# B137C.net
KiCad netlist of a schematic drawn in EAGLE
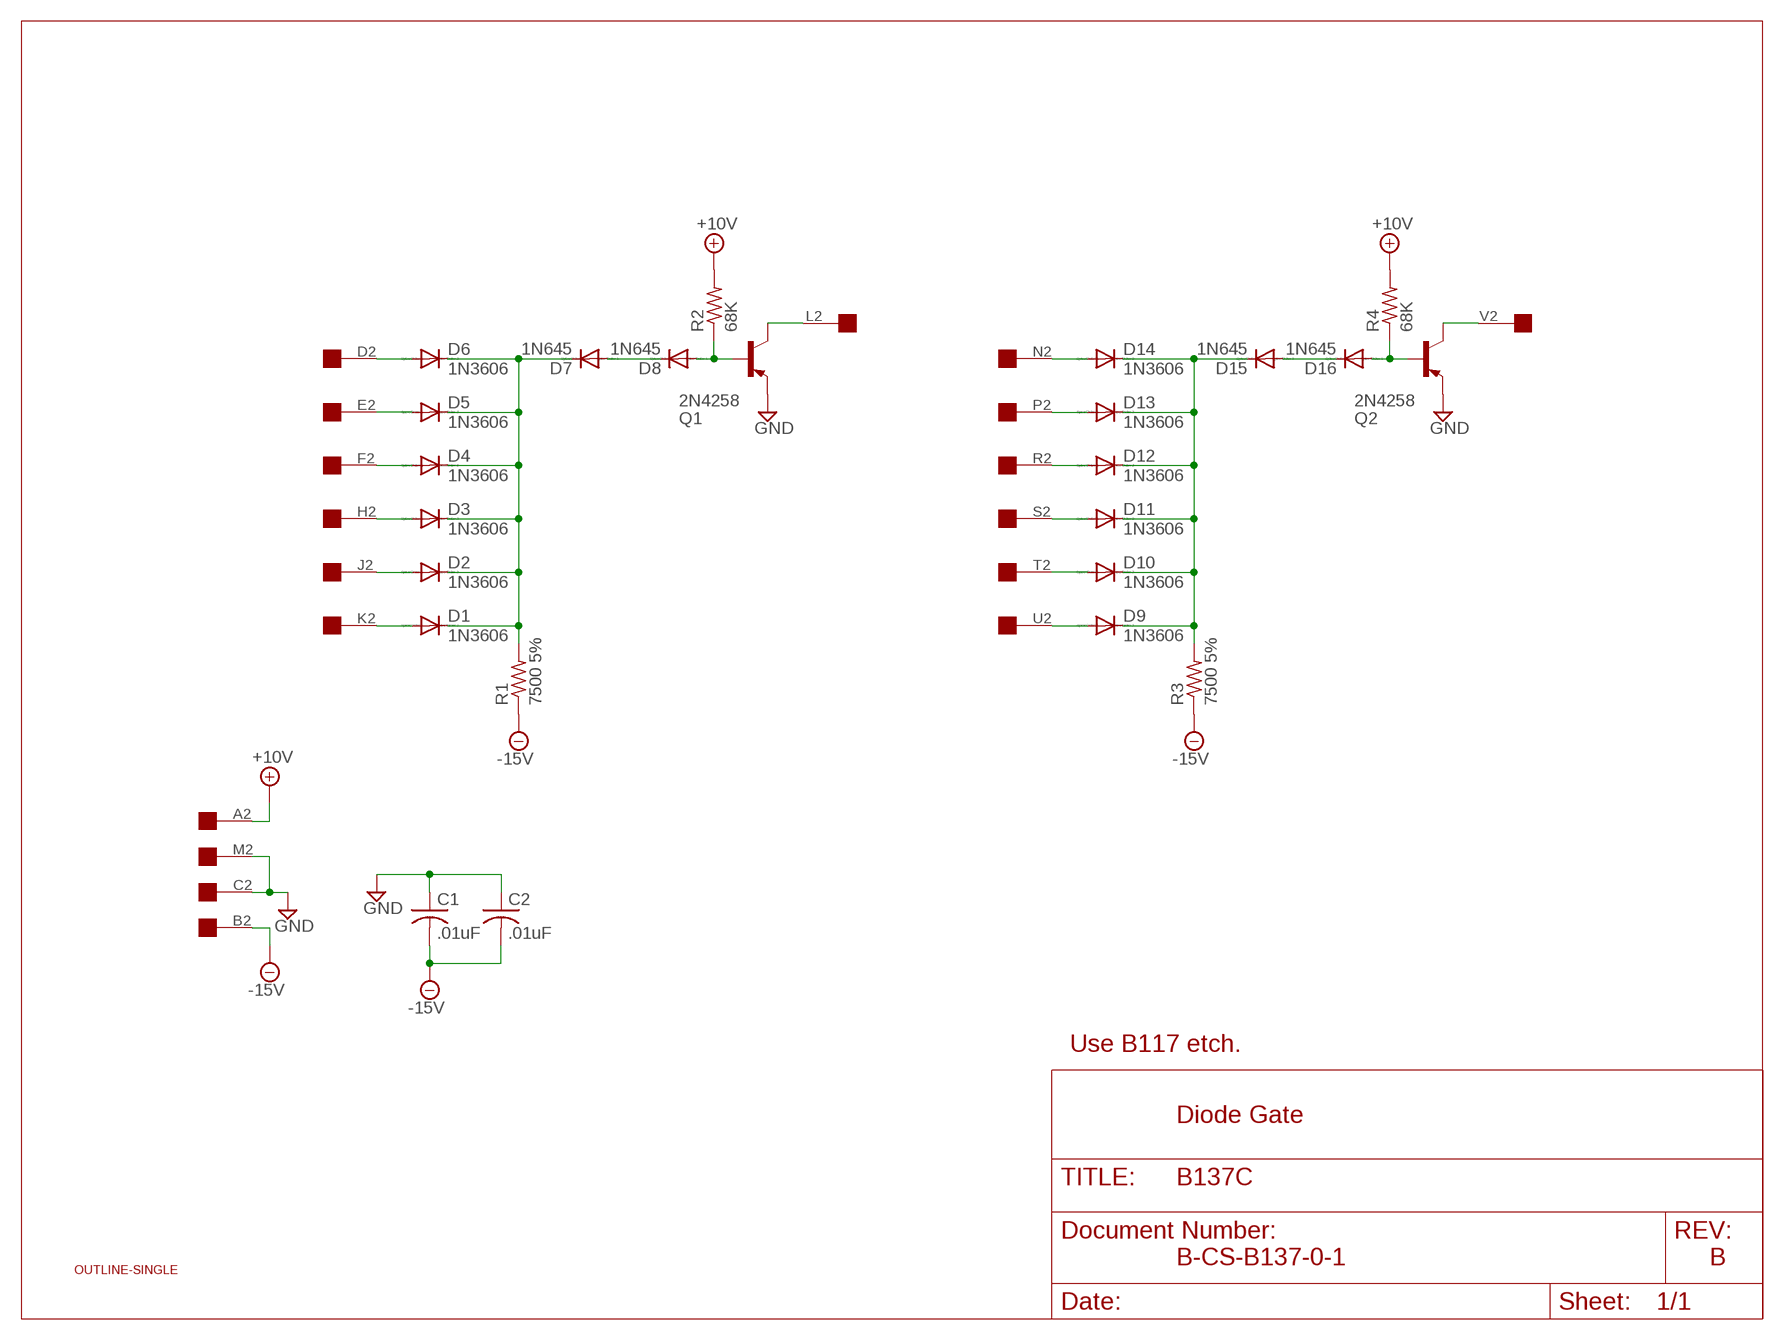
[diagram p0: schematic, sheet 1]

(export (version "E")
  (design (tool "Eeschema 10.0.6"))
  (components
    (comp (ref "C1")
      (value ".01uF")
      (footprint "eagle-import:C050-025X075")
      (libsource (lib "eagle-import") (part "C-US050-025X075"))
    )
    (comp (ref "C2")
      (value ".01uF")
      (footprint "eagle-import:C050-025X075")
      (libsource (lib "eagle-import") (part "C-US050-025X075"))
    )
    (comp (ref "D1")
      (value "1N3606")
      (footprint "eagle-import:DO35-10")
      (libsource (lib "eagle-import") (part "DIODE-DO35-10"))
    )
    (comp (ref "D2")
      (value "1N3606")
      (footprint "eagle-import:DO35-10")
      (libsource (lib "eagle-import") (part "DIODE-DO35-10"))
    )
    (comp (ref "D3")
      (value "1N3606")
      (footprint "eagle-import:DO35-10")
      (libsource (lib "eagle-import") (part "DIODE-DO35-10"))
    )
    (comp (ref "D4")
      (value "1N3606")
      (footprint "eagle-import:DO35-10")
      (libsource (lib "eagle-import") (part "DIODE-DO35-10"))
    )
    (comp (ref "D5")
      (value "1N3606")
      (footprint "eagle-import:DO35-10")
      (libsource (lib "eagle-import") (part "DIODE-DO35-10"))
    )
    (comp (ref "D6")
      (value "1N3606")
      (footprint "eagle-import:DO35-10")
      (libsource (lib "eagle-import") (part "DIODE-DO35-10"))
    )
    (comp (ref "D7")
      (value "1N645")
      (footprint "eagle-import:DO35-10")
      (libsource (lib "eagle-import") (part "DIODE-DO35-10"))
    )
    (comp (ref "D8")
      (value "1N645")
      (footprint "eagle-import:DO35-10")
      (libsource (lib "eagle-import") (part "DIODE-DO35-10"))
    )
    (comp (ref "D9")
      (value "1N3606")
      (footprint "eagle-import:DO35-10")
      (libsource (lib "eagle-import") (part "DIODE-DO35-10"))
    )
    (comp (ref "D10")
      (value "1N3606")
      (footprint "eagle-import:DO35-10")
      (libsource (lib "eagle-import") (part "DIODE-DO35-10"))
    )
    (comp (ref "D11")
      (value "1N3606")
      (footprint "eagle-import:DO35-10")
      (libsource (lib "eagle-import") (part "DIODE-DO35-10"))
    )
    (comp (ref "D12")
      (value "1N3606")
      (footprint "eagle-import:DO35-10")
      (libsource (lib "eagle-import") (part "DIODE-DO35-10"))
    )
    (comp (ref "D13")
      (value "1N3606")
      (footprint "eagle-import:DO35-10")
      (libsource (lib "eagle-import") (part "DIODE-DO35-10"))
    )
    (comp (ref "D14")
      (value "1N3606")
      (footprint "eagle-import:DO35-10")
      (libsource (lib "eagle-import") (part "DIODE-DO35-10"))
    )
    (comp (ref "D15")
      (value "1N645")
      (footprint "eagle-import:DO35-10")
      (libsource (lib "eagle-import") (part "DIODE-DO35-10"))
    )
    (comp (ref "D16")
      (value "1N645")
      (footprint "eagle-import:DO35-10")
      (libsource (lib "eagle-import") (part "DIODE-DO35-10"))
    )
    (comp (ref "Q1")
      (value "2N4258")
      (footprint "eagle-import:TO5")
      (libsource (lib "eagle-import") (part "-PNP-TO5"))
    )
    (comp (ref "Q2")
      (value "2N4258")
      (footprint "eagle-import:TO5")
      (libsource (lib "eagle-import") (part "-PNP-TO5"))
    )
    (comp (ref "R1")
      (value "7500 5%")
      (footprint "eagle-import:0207_10")
      (libsource (lib "eagle-import") (part "R-US_0207/10"))
    )
    (comp (ref "R2")
      (value "68K")
      (footprint "eagle-import:0207_10")
      (libsource (lib "eagle-import") (part "R-US_0207/10"))
    )
    (comp (ref "R3")
      (value "7500 5%")
      (footprint "eagle-import:0207_10")
      (libsource (lib "eagle-import") (part "R-US_0207/10"))
    )
    (comp (ref "R4")
      (value "68K")
      (footprint "eagle-import:0207_10")
      (libsource (lib "eagle-import") (part "R-US_0207/10"))
    )
    (comp (ref "U$1")
      (value "OUTLINE-SINGLE")
      (footprint "eagle-import:SINGLE")
      (libsource (lib "eagle-import") (part "OUTLINE-SINGLE"))
    )
    (comp (ref "U$2")
      (value "EDGE-1")
      (footprint "eagle-import:EDGE-CON1")
      (libsource (lib "eagle-import") (part "EDGE-1"))
    )
  )
  (nets
    (net (code "1") (name "+10V") (class "Default")
      (node (ref "R2") (pin "2") (pinfunction "2_2") (pintype "passive"))
      (node (ref "R4") (pin "2") (pinfunction "2_2") (pintype "passive"))
      (node (ref "U$2") (pin "A2") (pinfunction "1_A2") (pintype "bidirectional"))
    )
    (net (code "2") (name "-15V") (class "Default")
      (node (ref "C1") (pin "2") (pinfunction "2_2") (pintype "passive"))
      (node (ref "C2") (pin "2") (pinfunction "2_2") (pintype "passive"))
      (node (ref "R1") (pin "1") (pinfunction "1_1") (pintype "passive"))
      (node (ref "R3") (pin "1") (pinfunction "1_1") (pintype "passive"))
      (node (ref "U$2") (pin "B2") (pinfunction "1_B2") (pintype "bidirectional"))
    )
    (net (code "3") (name "GND") (class "Default")
      (node (ref "C1") (pin "1") (pinfunction "1_1") (pintype "passive"))
      (node (ref "C2") (pin "1") (pinfunction "1_1") (pintype "passive"))
      (node (ref "Q1") (pin "1") (pinfunction "E_1") (pintype "passive"))
      (node (ref "Q2") (pin "1") (pinfunction "E_1") (pintype "passive"))
      (node (ref "U$2") (pin "C2") (pinfunction "1_C2") (pintype "bidirectional"))
      (node (ref "U$2") (pin "M2") (pinfunction "1_M2") (pintype "bidirectional"))
    )
    (net (code "4") (name "Net-(D1-PadC)") (class "Default")
      (node (ref "D1") (pin "C") (pinfunction "C_C") (pintype "passive"))
      (node (ref "D2") (pin "C") (pinfunction "C_C") (pintype "passive"))
      (node (ref "D3") (pin "C") (pinfunction "C_C") (pintype "passive"))
      (node (ref "D4") (pin "C") (pinfunction "C_C") (pintype "passive"))
      (node (ref "D5") (pin "C") (pinfunction "C_C") (pintype "passive"))
      (node (ref "D6") (pin "C") (pinfunction "C_C") (pintype "passive"))
      (node (ref "D7") (pin "C") (pinfunction "C_C") (pintype "passive"))
      (node (ref "R1") (pin "2") (pinfunction "2_2") (pintype "passive"))
    )
    (net (code "5") (name "Net-(D7-PadA)") (class "Default")
      (node (ref "D7") (pin "A") (pinfunction "A_A") (pintype "passive"))
      (node (ref "D8") (pin "C") (pinfunction "C_C") (pintype "passive"))
    )
    (net (code "6") (name "Net-(D10-PadC)") (class "Default")
      (node (ref "D10") (pin "C") (pinfunction "C_C") (pintype "passive"))
      (node (ref "D11") (pin "C") (pinfunction "C_C") (pintype "passive"))
      (node (ref "D12") (pin "C") (pinfunction "C_C") (pintype "passive"))
      (node (ref "D13") (pin "C") (pinfunction "C_C") (pintype "passive"))
      (node (ref "D14") (pin "C") (pinfunction "C_C") (pintype "passive"))
      (node (ref "D15") (pin "C") (pinfunction "C_C") (pintype "passive"))
      (node (ref "D9") (pin "C") (pinfunction "C_C") (pintype "passive"))
      (node (ref "R3") (pin "2") (pinfunction "2_2") (pintype "passive"))
    )
    (net (code "7") (name "Net-(D15-PadA)") (class "Default")
      (node (ref "D15") (pin "A") (pinfunction "A_A") (pintype "passive"))
      (node (ref "D16") (pin "C") (pinfunction "C_C") (pintype "passive"))
    )
    (net (code "8") (name "Net-(Q1-B)") (class "Default")
      (node (ref "D8") (pin "A") (pinfunction "A_A") (pintype "passive"))
      (node (ref "Q1") (pin "2") (pinfunction "B_2") (pintype "passive"))
      (node (ref "R2") (pin "1") (pinfunction "1_1") (pintype "passive"))
    )
    (net (code "9") (name "Net-(Q1-C)") (class "Default")
      (node (ref "Q1") (pin "3") (pinfunction "C_3") (pintype "passive"))
      (node (ref "U$2") (pin "L2") (pinfunction "1_L2") (pintype "bidirectional"))
    )
    (net (code "10") (name "Net-(Q2-B)") (class "Default")
      (node (ref "D16") (pin "A") (pinfunction "A_A") (pintype "passive"))
      (node (ref "Q2") (pin "2") (pinfunction "B_2") (pintype "passive"))
      (node (ref "R4") (pin "1") (pinfunction "1_1") (pintype "passive"))
    )
    (net (code "11") (name "Net-(Q2-C)") (class "Default")
      (node (ref "Q2") (pin "3") (pinfunction "C_3") (pintype "passive"))
      (node (ref "U$2") (pin "V2") (pinfunction "1_V2") (pintype "bidirectional"))
    )
    (net (code "12") (name "Net-(U$2D-1)") (class "Default")
      (node (ref "D6") (pin "A") (pinfunction "A_A") (pintype "passive"))
      (node (ref "U$2") (pin "D2") (pinfunction "1_D2") (pintype "bidirectional"))
    )
    (net (code "13") (name "Net-(U$2E-1)") (class "Default")
      (node (ref "D5") (pin "A") (pinfunction "A_A") (pintype "passive"))
      (node (ref "U$2") (pin "E2") (pinfunction "1_E2") (pintype "bidirectional"))
    )
    (net (code "14") (name "Net-(U$2F-1)") (class "Default")
      (node (ref "D4") (pin "A") (pinfunction "A_A") (pintype "passive"))
      (node (ref "U$2") (pin "F2") (pinfunction "1_F2") (pintype "bidirectional"))
    )
    (net (code "15") (name "Net-(U$2G-1)") (class "Default")
      (node (ref "D3") (pin "A") (pinfunction "A_A") (pintype "passive"))
      (node (ref "U$2") (pin "H2") (pinfunction "1_H2") (pintype "bidirectional"))
    )
    (net (code "16") (name "Net-(U$2H-1)") (class "Default")
      (node (ref "D2") (pin "A") (pinfunction "A_A") (pintype "passive"))
      (node (ref "U$2") (pin "J2") (pinfunction "1_J2") (pintype "bidirectional"))
    )
    (net (code "17") (name "Net-(U$2I-1)") (class "Default")
      (node (ref "D1") (pin "A") (pinfunction "A_A") (pintype "passive"))
      (node (ref "U$2") (pin "K2") (pinfunction "1_K2") (pintype "bidirectional"))
    )
    (net (code "18") (name "Net-(U$2L-1)") (class "Default")
      (node (ref "D14") (pin "A") (pinfunction "A_A") (pintype "passive"))
      (node (ref "U$2") (pin "N2") (pinfunction "1_N2") (pintype "bidirectional"))
    )
    (net (code "19") (name "Net-(U$2M-1)") (class "Default")
      (node (ref "D13") (pin "A") (pinfunction "A_A") (pintype "passive"))
      (node (ref "U$2") (pin "P2") (pinfunction "1_P2") (pintype "bidirectional"))
    )
    (net (code "20") (name "Net-(U$2N-1)") (class "Default")
      (node (ref "D12") (pin "A") (pinfunction "A_A") (pintype "passive"))
      (node (ref "U$2") (pin "R2") (pinfunction "1_R2") (pintype "bidirectional"))
    )
    (net (code "21") (name "Net-(U$2O-1)") (class "Default")
      (node (ref "D11") (pin "A") (pinfunction "A_A") (pintype "passive"))
      (node (ref "U$2") (pin "S2") (pinfunction "1_S2") (pintype "bidirectional"))
    )
    (net (code "22") (name "Net-(U$2P-1)") (class "Default")
      (node (ref "D10") (pin "A") (pinfunction "A_A") (pintype "passive"))
      (node (ref "U$2") (pin "T2") (pinfunction "1_T2") (pintype "bidirectional"))
    )
    (net (code "23") (name "Net-(U$2Q-1)") (class "Default")
      (node (ref "D9") (pin "A") (pinfunction "A_A") (pintype "passive"))
      (node (ref "U$2") (pin "U2") (pinfunction "1_U2") (pintype "bidirectional"))
    )
  )
)
